# MSP432E401YTPDT_MCU.net
KiCad netlist of a schematic drawn in Altium Designer
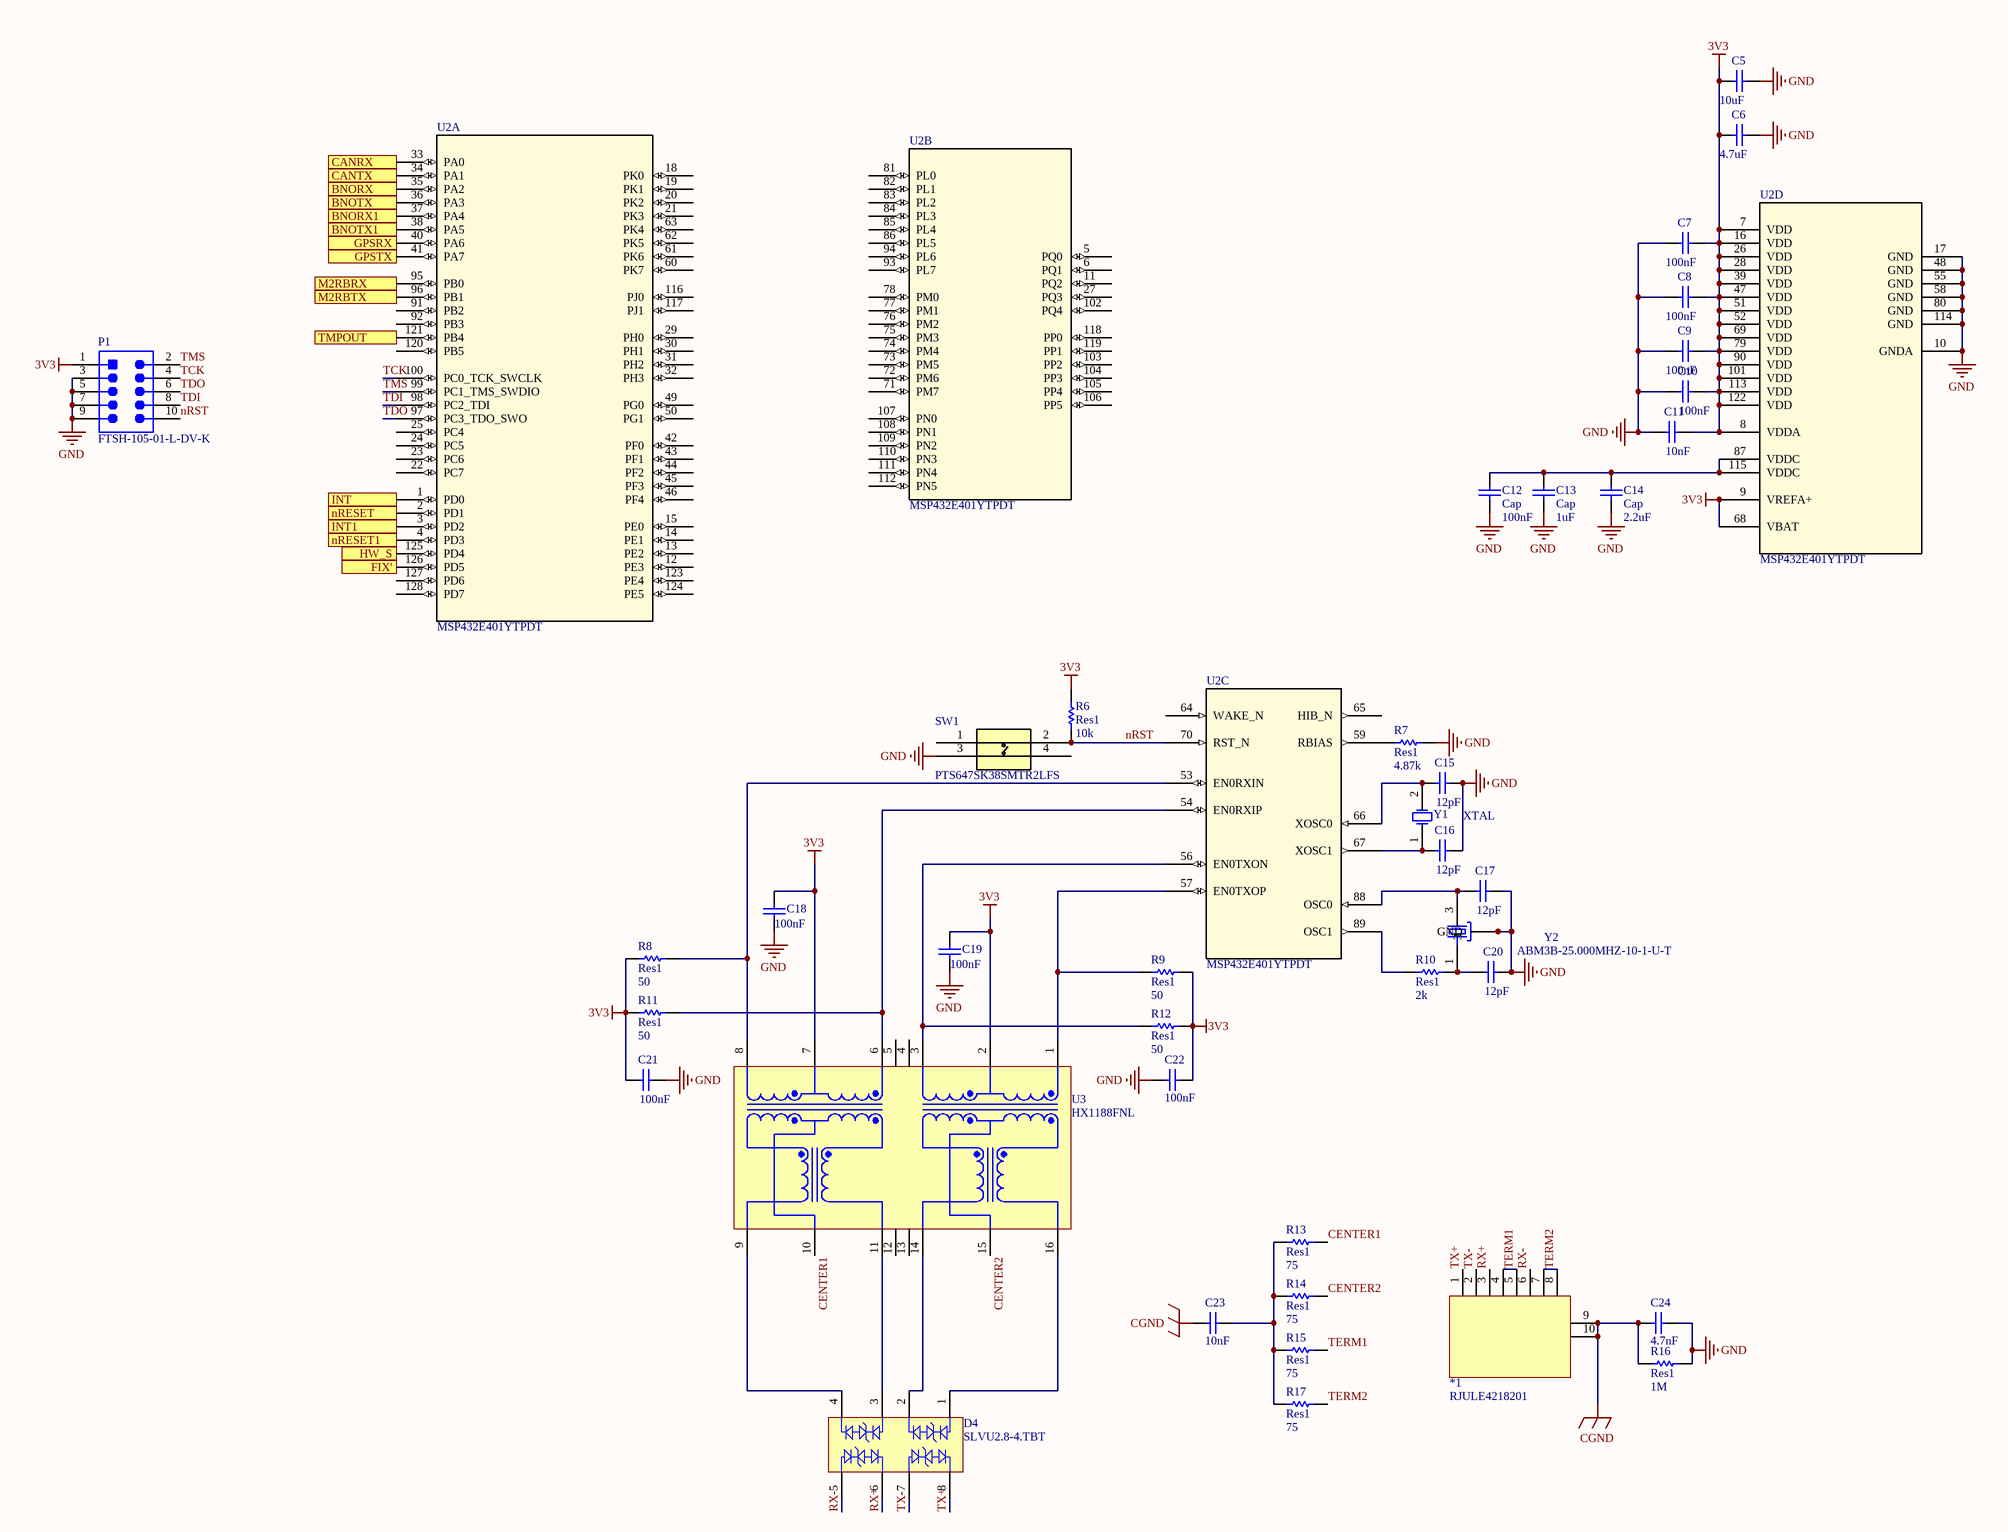
[diagram p0: MSP432E401YTPDT MCU.SchDoc]

(export (version "E")
  (design (tool "Eeschema 10.0.6"))
  (components
    (comp (ref "*1")
      (value "RJULE4218201")
      (footprint "RJULE4218201")
      (libsource (lib "RJULE4218201") (part "RJULE4218201"))
    )
    (comp (ref "C5")
      (value "10uF")
      (footprint "6-0805_M")
      (description "Capacitor")
      (fields (field (name "Comment") "Cap") (field (name "PUBLISHER") "Altium Limited"))
      (libsource (lib "Miscellaneous Devices") (part "Cap"))
    )
    (comp (ref "C6")
      (value "4.7uF")
      (footprint "6-0805_M")
      (description "Capacitor")
      (fields (field (name "Comment") "Cap") (field (name "PUBLISHER") "Altium Limited"))
      (libsource (lib "Miscellaneous Devices") (part "Cap"))
    )
    (comp (ref "C7")
      (value "100nF")
      (footprint "0402-A")
      (description "Capacitor")
      (fields (field (name "Comment") "Cap") (field (name "PUBLISHER") "Altium Limited"))
      (libsource (lib "Miscellaneous Devices") (part "Cap"))
    )
    (comp (ref "C8")
      (value "100nF")
      (footprint "0402-A")
      (description "Capacitor")
      (fields (field (name "Comment") "Cap") (field (name "PUBLISHER") "Altium Limited"))
      (libsource (lib "Miscellaneous Devices") (part "Cap"))
    )
    (comp (ref "C9")
      (value "100nF")
      (footprint "0402-A")
      (description "Capacitor")
      (fields (field (name "Comment") "Cap") (field (name "PUBLISHER") "Altium Limited"))
      (libsource (lib "Miscellaneous Devices") (part "Cap"))
    )
    (comp (ref "C10")
      (value "100nF")
      (footprint "0402-A")
      (description "Capacitor")
      (fields (field (name "Comment") "Cap") (field (name "PUBLISHER") "Altium Limited"))
      (libsource (lib "Miscellaneous Devices") (part "Cap"))
    )
    (comp (ref "C11")
      (value "10nF")
      (footprint "0402-A")
      (description "Capacitor")
      (fields (field (name "Comment") "Cap") (field (name "PUBLISHER") "Altium Limited"))
      (libsource (lib "Miscellaneous Devices") (part "Cap"))
    )
    (comp (ref "C12")
      (value "Cap")
      (footprint "0402-A")
      (description "Capacitor")
      (fields (field (name "ALTIUM_VALUE") "100nF") (field (name "PUBLISHER") "Altium Limited"))
      (libsource (lib "Miscellaneous Devices") (part "Cap"))
    )
    (comp (ref "C13")
      (value "Cap")
      (footprint "1608[0603]")
      (description "Capacitor")
      (fields (field (name "ALTIUM_VALUE") "1uF") (field (name "PUBLISHER") "Altium Limited"))
      (libsource (lib "Miscellaneous Devices") (part "Cap"))
    )
    (comp (ref "C14")
      (value "Cap")
      (footprint "1608[0603]")
      (description "Capacitor")
      (fields (field (name "ALTIUM_VALUE") "2.2uF") (field (name "PUBLISHER") "Altium Limited"))
      (libsource (lib "Miscellaneous Devices") (part "Cap"))
    )
    (comp (ref "C15")
      (value "12pF")
      (footprint "0402-A")
      (description "Capacitor")
      (fields (field (name "Comment") "Cap") (field (name "PUBLISHER") "Altium Limited"))
      (libsource (lib "Miscellaneous Devices") (part "Cap"))
    )
    (comp (ref "C16")
      (value "12pF")
      (footprint "0402-A")
      (description "Capacitor")
      (fields (field (name "Comment") "Cap") (field (name "PUBLISHER") "Altium Limited"))
      (libsource (lib "Miscellaneous Devices") (part "Cap"))
    )
    (comp (ref "C17")
      (value "12pF")
      (footprint "0402-A")
      (description "Capacitor")
      (fields (field (name "Comment") "Cap") (field (name "PUBLISHER") "Altium Limited"))
      (libsource (lib "Miscellaneous Devices") (part "Cap"))
    )
    (comp (ref "C18")
      (value "100nF")
      (footprint "0402-A")
      (description "Capacitor")
      (fields (field (name "Comment") "Cap") (field (name "PUBLISHER") "Altium Limited"))
      (libsource (lib "Miscellaneous Devices") (part "Cap"))
    )
    (comp (ref "C19")
      (value "100nF")
      (footprint "0402-A")
      (description "Capacitor")
      (fields (field (name "Comment") "Cap") (field (name "PUBLISHER") "Altium Limited"))
      (libsource (lib "Miscellaneous Devices") (part "Cap"))
    )
    (comp (ref "C20")
      (value "12pF")
      (footprint "0402-A")
      (description "Capacitor")
      (fields (field (name "Comment") "Cap") (field (name "PUBLISHER") "Altium Limited"))
      (libsource (lib "Miscellaneous Devices") (part "Cap"))
    )
    (comp (ref "C21")
      (value "100nF")
      (footprint "0402-A")
      (description "Capacitor")
      (fields (field (name "Comment") "Cap") (field (name "PUBLISHER") "Altium Limited"))
      (libsource (lib "Miscellaneous Devices") (part "Cap"))
    )
    (comp (ref "C22")
      (value "100nF")
      (footprint "0402-A")
      (description "Capacitor")
      (fields (field (name "Comment") "Cap") (field (name "PUBLISHER") "Altium Limited"))
      (libsource (lib "Miscellaneous Devices") (part "Cap"))
    )
    (comp (ref "C23")
      (value "10nF")
      (footprint "0402-A")
      (description "Capacitor")
      (fields (field (name "Comment") "Cap") (field (name "PUBLISHER") "Altium Limited"))
      (libsource (lib "Miscellaneous Devices") (part "Cap"))
    )
    (comp (ref "C24")
      (value "4.7nF")
      (footprint "C1206")
      (description "Capacitor")
      (fields (field (name "Comment") "Cap") (field (name "PUBLISHER") "Altium Limited"))
      (libsource (lib "Miscellaneous Devices") (part "Cap"))
    )
    (comp (ref "D4")
      (value "SLVU2.8-4.TBT")
      (footprint "SEMT-SO-8_V")
      (fields (field (name "MANUFACTURER") "Semtech"))
      (libsource (lib "Altium Content Vault") (part "SEMT-SLVU2.8-4-SO-8"))
    )
    (comp (ref "P1")
      (value "FTSH-105-01-L-DV-K")
      (footprint "SMTC-FTSH-105-01-L-DV-K_V")
      (description "Male Header, Pitch 1.27 mm, 2 x 5 Position, Height 6.25 mm")
      (fields (field (name "MANUFACTURER") "Samtec"))
      (libsource (lib "Altium Content Vault") (part "CN-2P-M-R10"))
    )
    (comp (ref "R6")
      (value "Res1")
      (footprint "0402-A")
      (description "Resistor")
      (fields (field (name "ALTIUM_VALUE") "10k") (field (name "PUBLISHER") "Altium Limited"))
      (libsource (lib "Miscellaneous Devices") (part "Res1"))
    )
    (comp (ref "R7")
      (value "Res1")
      (footprint "0402-A")
      (description "Resistor")
      (fields (field (name "ALTIUM_VALUE") "4.87k") (field (name "PUBLISHER") "Altium Limited"))
      (libsource (lib "Miscellaneous Devices") (part "Res1"))
    )
    (comp (ref "R8")
      (value "Res1")
      (footprint "0402-A")
      (description "Resistor")
      (fields (field (name "ALTIUM_VALUE") "50") (field (name "PUBLISHER") "Altium Limited"))
      (libsource (lib "Miscellaneous Devices") (part "Res1"))
    )
    (comp (ref "R9")
      (value "Res1")
      (footprint "0402-A")
      (description "Resistor")
      (fields (field (name "ALTIUM_VALUE") "50") (field (name "PUBLISHER") "Altium Limited"))
      (libsource (lib "Miscellaneous Devices") (part "Res1"))
    )
    (comp (ref "R10")
      (value "Res1")
      (footprint "0402-A")
      (description "Resistor")
      (fields (field (name "ALTIUM_VALUE") "2k") (field (name "PUBLISHER") "Altium Limited"))
      (libsource (lib "Miscellaneous Devices") (part "Res1"))
    )
    (comp (ref "R11")
      (value "Res1")
      (footprint "0402-A")
      (description "Resistor")
      (fields (field (name "ALTIUM_VALUE") "50") (field (name "PUBLISHER") "Altium Limited"))
      (libsource (lib "Miscellaneous Devices") (part "Res1"))
    )
    (comp (ref "R12")
      (value "Res1")
      (footprint "0402-A")
      (description "Resistor")
      (fields (field (name "ALTIUM_VALUE") "50") (field (name "PUBLISHER") "Altium Limited"))
      (libsource (lib "Miscellaneous Devices") (part "Res1"))
    )
    (comp (ref "R13")
      (value "Res1")
      (footprint "0402-A")
      (description "Resistor")
      (fields (field (name "ALTIUM_VALUE") "75") (field (name "PUBLISHER") "Altium Limited"))
      (libsource (lib "Miscellaneous Devices") (part "Res1"))
    )
    (comp (ref "R14")
      (value "Res1")
      (footprint "0402-A")
      (description "Resistor")
      (fields (field (name "ALTIUM_VALUE") "75") (field (name "PUBLISHER") "Altium Limited"))
      (libsource (lib "Miscellaneous Devices") (part "Res1"))
    )
    (comp (ref "R15")
      (value "Res1")
      (footprint "0402-A")
      (description "Resistor")
      (fields (field (name "ALTIUM_VALUE") "75") (field (name "PUBLISHER") "Altium Limited"))
      (libsource (lib "Miscellaneous Devices") (part "Res1"))
    )
    (comp (ref "R16")
      (value "Res1")
      (footprint "C1206")
      (description "Resistor")
      (fields (field (name "ALTIUM_VALUE") "1M") (field (name "PUBLISHER") "Altium Limited"))
      (libsource (lib "Miscellaneous Devices") (part "Res1"))
    )
    (comp (ref "R17")
      (value "Res1")
      (footprint "0402-A")
      (description "Resistor")
      (fields (field (name "ALTIUM_VALUE") "75") (field (name "PUBLISHER") "Altium Limited"))
      (libsource (lib "Miscellaneous Devices") (part "Res1"))
    )
    (comp (ref "SW1")
      (value "PTS647SK38SMTR2LFS")
      (footprint "PTS647SK38SMTR2LFS_CNK")
      (description "No Description Available")
      (fields (field (name "COPYRIGHT") "Copyright (C) 2018 Accelerated Designs. All rights reserved"))
      (libsource (lib "PTS 647 SK38 SMTR2 LFS") (part "PTS647SK38SMTR2LFS"))
    )
    (comp (ref "U2")
      (value "MSP432E401YTPDT")
      (footprint "PDT0128A")
      (description "No Description Available")
      (fields
        (field (name "MANUFACTURER") "Texas Instruments")
        (field (name "PARTNUMBER") "MSP432E401YTPDTR")
        (field (name "COPYRIGHT") "Copyright (C) 2018 Accelerated Designs. All rights reserved")
      )
      (libsource (lib "MSP432E401Y") (part "MSP432E401YTPDT"))
    )
    (comp (ref "U3")
      (value "HX1188FNL")
      (footprint "PULS-HX1188FNL-SMT-16_V")
      (description "Telecom Transformer 1:1/1:1, -40 to 85 degC, 16-Pin SMT, RoHS, Tube")
      (fields (field (name "MANUFACTURER") "Pulse Electronics"))
      (libsource (lib "Altium Content Vault") (part "PULS-HX1188FNL-16"))
    )
    (comp (ref "Y1")
      (value "XTAL")
      (footprint "FC-135 32.7680KA-AC0")
      (description "Crystal Oscillator")
      (fields (field (name "PUBLISHER") "Altium Limited"))
      (libsource (lib "Miscellaneous Devices") (part "XTAL"))
    )
    (comp (ref "Y2")
      (value "ABM3B-25.000MHZ-10-1-U-T")
      (footprint "OSCCC500X320X110-4N")
      (description "25MHz Â±10ppm Crystal 10pF 50 Ohms 4-SMD, No Lead")
      (fields (field (name "MF") "Abracon"))
      (libsource (lib "ABM3B-25.000MHZ-10-1-U-T") (part "ABM3B-25.000MHZ-10-1-U-T"))
    )
  )
  (nets
    (net (code "1") (name "/BNORX") (class "Default")
      (node (ref "U2") (pin "35") (pinfunction "PA2_35") (pintype "bidirectional"))
    )
    (net (code "2") (name "/BNORX1") (class "Default")
      (node (ref "U2") (pin "37") (pinfunction "PA4_37") (pintype "bidirectional"))
    )
    (net (code "3") (name "/BNOTX") (class "Default")
      (node (ref "U2") (pin "36") (pinfunction "PA3_36") (pintype "bidirectional"))
    )
    (net (code "4") (name "/BNOTX1") (class "Default")
      (node (ref "U2") (pin "38") (pinfunction "PA5_38") (pintype "bidirectional"))
    )
    (net (code "5") (name "/CANRX") (class "Default")
      (node (ref "U2") (pin "33") (pinfunction "PA0_33") (pintype "bidirectional"))
    )
    (net (code "6") (name "/CANTX") (class "Default")
      (node (ref "U2") (pin "34") (pinfunction "PA1_34") (pintype "bidirectional"))
    )
    (net (code "7") (name "/CENTER1") (class "Default")
      (node (ref "R13") (pin "2") (pinfunction "2_2") (pintype "passive"))
      (node (ref "U3") (pin "10") (pinfunction "CMT_10") (pintype "passive"))
    )
    (net (code "8") (name "/CENTER2") (class "Default")
      (node (ref "R14") (pin "2") (pinfunction "2_2") (pintype "passive"))
      (node (ref "U3") (pin "15") (pinfunction "CMT_15") (pintype "passive"))
    )
    (net (code "9") (name "/FIX'") (class "Default")
      (node (ref "U2") (pin "126") (pinfunction "PD5_126") (pintype "bidirectional"))
    )
    (net (code "10") (name "/GPSRX") (class "Default")
      (node (ref "U2") (pin "40") (pinfunction "PA6_40") (pintype "bidirectional"))
    )
    (net (code "11") (name "/GPSTX") (class "Default")
      (node (ref "U2") (pin "41") (pinfunction "PA7_41") (pintype "bidirectional"))
    )
    (net (code "12") (name "/HW_S") (class "Default")
      (node (ref "U2") (pin "125") (pinfunction "PD4_125") (pintype "bidirectional"))
    )
    (net (code "13") (name "/INT") (class "Default")
      (node (ref "U2") (pin "1") (pinfunction "PD0_1") (pintype "bidirectional"))
    )
    (net (code "14") (name "/INT1") (class "Default")
      (node (ref "U2") (pin "3") (pinfunction "PD2_3") (pintype "bidirectional"))
    )
    (net (code "15") (name "/M2RBRX") (class "Default")
      (node (ref "U2") (pin "95") (pinfunction "PB0_95") (pintype "bidirectional"))
    )
    (net (code "16") (name "/M2RBTX") (class "Default")
      (node (ref "U2") (pin "96") (pinfunction "PB1_96") (pintype "bidirectional"))
    )
    (net (code "17") (name "/RX+") (class "Default")
      (node (ref "*1") (pin "3") (pinfunction "13_3") (pintype "passive"))
      (node (ref "D4") (pin "6") (pinfunction "6_6") (pintype "passive"))
    )
    (net (code "18") (name "/RX-") (class "Default")
      (node (ref "*1") (pin "6") (pinfunction "16_6") (pintype "passive"))
      (node (ref "D4") (pin "5") (pinfunction "5_5") (pintype "passive"))
    )
    (net (code "19") (name "/TCK") (class "Default")
      (node (ref "P1") (pin "4") (pinfunction "4_4") (pintype "passive"))
      (node (ref "U2") (pin "100") (pinfunction "PC0_TCK_SWCLK_100") (pintype "bidirectional"))
    )
    (net (code "20") (name "/TDI") (class "Default")
      (node (ref "P1") (pin "8") (pinfunction "8_8") (pintype "passive"))
      (node (ref "U2") (pin "98") (pinfunction "PC2_TDI_98") (pintype "bidirectional"))
    )
    (net (code "21") (name "/TDO") (class "Default")
      (node (ref "P1") (pin "6") (pinfunction "6_6") (pintype "passive"))
      (node (ref "U2") (pin "97") (pinfunction "PC3_TDO_SWO_97") (pintype "bidirectional"))
    )
    (net (code "22") (name "/TERM1") (class "Default")
      (node (ref "*1") (pin "4") (pinfunction "14_4") (pintype "passive"))
      (node (ref "*1") (pin "5") (pinfunction "15_5") (pintype "passive"))
      (node (ref "R15") (pin "2") (pinfunction "2_2") (pintype "passive"))
    )
    (net (code "23") (name "/TERM2") (class "Default")
      (node (ref "*1") (pin "7") (pinfunction "17_7") (pintype "passive"))
      (node (ref "*1") (pin "8") (pinfunction "18_8") (pintype "passive"))
      (node (ref "R17") (pin "2") (pinfunction "2_2") (pintype "passive"))
    )
    (net (code "24") (name "/TMPOUT") (class "Default")
      (node (ref "U2") (pin "121") (pinfunction "PB4_121") (pintype "bidirectional"))
    )
    (net (code "25") (name "/TMS") (class "Default")
      (node (ref "P1") (pin "2") (pinfunction "2_2") (pintype "passive"))
      (node (ref "U2") (pin "99") (pinfunction "PC1_TMS_SWDIO_99") (pintype "bidirectional"))
    )
    (net (code "26") (name "/TX+") (class "Default")
      (node (ref "*1") (pin "1") (pinfunction "11_1") (pintype "passive"))
      (node (ref "D4") (pin "8") (pinfunction "8_8") (pintype "passive"))
    )
    (net (code "27") (name "/TX-") (class "Default")
      (node (ref "*1") (pin "2") (pinfunction "12_2") (pintype "passive"))
      (node (ref "D4") (pin "7") (pinfunction "7_7") (pintype "passive"))
    )
    (net (code "28") (name "/nRESET") (class "Default")
      (node (ref "U2") (pin "2") (pinfunction "PD1_2") (pintype "bidirectional"))
    )
    (net (code "29") (name "/nRESET1") (class "Default")
      (node (ref "U2") (pin "4") (pinfunction "PD3_4") (pintype "bidirectional"))
    )
    (net (code "30") (name "/nRST") (class "Default")
      (node (ref "P1") (pin "10") (pinfunction "10_10") (pintype "passive"))
      (node (ref "R6") (pin "2") (pinfunction "2_2") (pintype "passive"))
      (node (ref "SW1") (pin "2") (pinfunction "2_2") (pintype "passive"))
      (node (ref "U2") (pin "70") (pinfunction "RST_N_70") (pintype "input"))
    )
    (net (code "31") (name "3V3") (class "Default")
      (node (ref "C10") (pin "2") (pinfunction "2_2") (pintype "passive"))
      (node (ref "C11") (pin "2") (pinfunction "2_2") (pintype "passive"))
      (node (ref "C18") (pin "1") (pinfunction "1_1") (pintype "passive"))
      (node (ref "C19") (pin "1") (pinfunction "1_1") (pintype "passive"))
      (node (ref "C21") (pin "1") (pinfunction "1_1") (pintype "passive"))
      (node (ref "C22") (pin "1") (pinfunction "1_1") (pintype "passive"))
      (node (ref "C5") (pin "1") (pinfunction "1_1") (pintype "passive"))
      (node (ref "C6") (pin "1") (pinfunction "1_1") (pintype "passive"))
      (node (ref "C7") (pin "2") (pinfunction "2_2") (pintype "passive"))
      (node (ref "C8") (pin "2") (pinfunction "2_2") (pintype "passive"))
      (node (ref "C9") (pin "2") (pinfunction "2_2") (pintype "passive"))
      (node (ref "P1") (pin "1") (pinfunction "1_1") (pintype "passive"))
      (node (ref "R11") (pin "1") (pinfunction "1_1") (pintype "passive"))
      (node (ref "R12") (pin "1") (pinfunction "1_1") (pintype "passive"))
      (node (ref "R6") (pin "1") (pinfunction "1_1") (pintype "passive"))
      (node (ref "R8") (pin "1") (pinfunction "1_1") (pintype "passive"))
      (node (ref "R9") (pin "1") (pinfunction "1_1") (pintype "passive"))
      (node (ref "U2") (pin "101") (pinfunction "VDD_101") (pintype "power_in"))
      (node (ref "U2") (pin "113") (pinfunction "VDD_113") (pintype "power_in"))
      (node (ref "U2") (pin "122") (pinfunction "VDD_122") (pintype "power_in"))
      (node (ref "U2") (pin "16") (pinfunction "VDD_16") (pintype "power_in"))
      (node (ref "U2") (pin "26") (pinfunction "VDD_26") (pintype "power_in"))
      (node (ref "U2") (pin "28") (pinfunction "VDD_28") (pintype "power_in"))
      (node (ref "U2") (pin "39") (pinfunction "VDD_39") (pintype "power_in"))
      (node (ref "U2") (pin "47") (pinfunction "VDD_47") (pintype "power_in"))
      (node (ref "U2") (pin "51") (pinfunction "VDD_51") (pintype "power_in"))
      (node (ref "U2") (pin "52") (pinfunction "VDD_52") (pintype "power_in"))
      (node (ref "U2") (pin "68") (pinfunction "VBAT_68") (pintype "power_in"))
      (node (ref "U2") (pin "69") (pinfunction "VDD_69") (pintype "power_in"))
      (node (ref "U2") (pin "7") (pinfunction "VDD_7") (pintype "power_in"))
      (node (ref "U2") (pin "79") (pinfunction "VDD_79") (pintype "power_in"))
      (node (ref "U2") (pin "8") (pinfunction "VDDA_8") (pintype "power_in"))
      (node (ref "U2") (pin "9") (pinfunction "VREFA+_9") (pintype "power_in"))
      (node (ref "U2") (pin "90") (pinfunction "VDD_90") (pintype "power_in"))
      (node (ref "U3") (pin "2") (pinfunction "TCT_2") (pintype "passive"))
      (node (ref "U3") (pin "7") (pinfunction "RCT_7") (pintype "passive"))
    )
    (net (code "32") (name "CGND") (class "Default")
      (node (ref "*1") (pin "10") (pinfunction "10_10") (pintype "passive"))
      (node (ref "*1") (pin "9") (pinfunction "9_9") (pintype "passive"))
      (node (ref "C23") (pin "1") (pinfunction "1_1") (pintype "passive"))
      (node (ref "C24") (pin "1") (pinfunction "1_1") (pintype "passive"))
      (node (ref "R16") (pin "1") (pinfunction "1_1") (pintype "passive"))
    )
    (net (code "33") (name "GND") (class "Default")
      (node (ref "C10") (pin "1") (pinfunction "1_1") (pintype "passive"))
      (node (ref "C11") (pin "1") (pinfunction "1_1") (pintype "passive"))
      (node (ref "C12") (pin "1") (pinfunction "1_1") (pintype "passive"))
      (node (ref "C13") (pin "1") (pinfunction "1_1") (pintype "passive"))
      (node (ref "C14") (pin "1") (pinfunction "1_1") (pintype "passive"))
      (node (ref "C15") (pin "1") (pinfunction "1_1") (pintype "passive"))
      (node (ref "C16") (pin "1") (pinfunction "1_1") (pintype "passive"))
      (node (ref "C17") (pin "1") (pinfunction "1_1") (pintype "passive"))
      (node (ref "C18") (pin "2") (pinfunction "2_2") (pintype "passive"))
      (node (ref "C19") (pin "2") (pinfunction "2_2") (pintype "passive"))
      (node (ref "C20") (pin "1") (pinfunction "1_1") (pintype "passive"))
      (node (ref "C21") (pin "2") (pinfunction "2_2") (pintype "passive"))
      (node (ref "C22") (pin "2") (pinfunction "2_2") (pintype "passive"))
      (node (ref "C24") (pin "2") (pinfunction "2_2") (pintype "passive"))
      (node (ref "C5") (pin "2") (pinfunction "2_2") (pintype "passive"))
      (node (ref "C6") (pin "2") (pinfunction "2_2") (pintype "passive"))
      (node (ref "C7") (pin "1") (pinfunction "1_1") (pintype "passive"))
      (node (ref "C8") (pin "1") (pinfunction "1_1") (pintype "passive"))
      (node (ref "C9") (pin "1") (pinfunction "1_1") (pintype "passive"))
      (node (ref "P1") (pin "3") (pinfunction "3_3") (pintype "passive"))
      (node (ref "P1") (pin "5") (pinfunction "5_5") (pintype "passive"))
      (node (ref "P1") (pin "7") (pinfunction "7_7") (pintype "passive"))
      (node (ref "P1") (pin "9") (pinfunction "9_9") (pintype "passive"))
      (node (ref "R16") (pin "2") (pinfunction "2_2") (pintype "passive"))
      (node (ref "R7") (pin "1") (pinfunction "1_1") (pintype "passive"))
      (node (ref "SW1") (pin "3") (pinfunction "3_3") (pintype "passive"))
      (node (ref "U2") (pin "10") (pinfunction "GNDA_10") (pintype "power_in"))
      (node (ref "U2") (pin "114") (pinfunction "GND_114") (pintype "power_in"))
      (node (ref "U2") (pin "17") (pinfunction "GND_17") (pintype "power_in"))
      (node (ref "U2") (pin "48") (pinfunction "GND_48") (pintype "power_in"))
      (node (ref "U2") (pin "55") (pinfunction "GND_55") (pintype "power_in"))
      (node (ref "U2") (pin "58") (pinfunction "GND_58") (pintype "power_in"))
      (node (ref "U2") (pin "80") (pinfunction "GND_80") (pintype "power_in"))
      (node (ref "Y2") (pin "2") (pinfunction "GND_2") (pintype "passive"))
      (node (ref "Y2") (pin "4") (pinfunction "GND_4") (pintype "passive"))
    )
    (net (code "34") (name "Net-(C12-Pad2)") (class "Default")
      (node (ref "C12") (pin "2") (pinfunction "2_2") (pintype "passive"))
      (node (ref "C13") (pin "2") (pinfunction "2_2") (pintype "passive"))
      (node (ref "C14") (pin "2") (pinfunction "2_2") (pintype "passive"))
      (node (ref "U2") (pin "115") (pinfunction "VDDC_115") (pintype "power_in"))
      (node (ref "U2") (pin "87") (pinfunction "VDDC_87") (pintype "power_in"))
    )
    (net (code "35") (name "Net-(C20-Pad2)") (class "Default")
      (node (ref "C20") (pin "2") (pinfunction "2_2") (pintype "passive"))
      (node (ref "R10") (pin "2") (pinfunction "2_2") (pintype "passive"))
      (node (ref "Y2") (pin "1") (pinfunction "1_1") (pintype "passive"))
    )
    (net (code "36") (name "Net-(C23-Pad2)") (class "Default")
      (node (ref "C23") (pin "2") (pinfunction "2_2") (pintype "passive"))
      (node (ref "R13") (pin "1") (pinfunction "1_1") (pintype "passive"))
      (node (ref "R14") (pin "1") (pinfunction "1_1") (pintype "passive"))
      (node (ref "R15") (pin "1") (pinfunction "1_1") (pintype "passive"))
      (node (ref "R17") (pin "1") (pinfunction "1_1") (pintype "passive"))
    )
    (net (code "37") (name "Net-(U2C-EN0RXIN)") (class "Default")
      (node (ref "R8") (pin "2") (pinfunction "2_2") (pintype "passive"))
      (node (ref "U2") (pin "53") (pinfunction "EN0RXIN_53") (pintype "bidirectional"))
      (node (ref "U3") (pin "8") (pinfunction "RD-_8") (pintype "passive"))
    )
    (net (code "38") (name "Net-(U2C-EN0RXIP)") (class "Default")
      (node (ref "R11") (pin "2") (pinfunction "2_2") (pintype "passive"))
      (node (ref "U2") (pin "54") (pinfunction "EN0RXIP_54") (pintype "bidirectional"))
      (node (ref "U3") (pin "6") (pinfunction "RD+_6") (pintype "passive"))
    )
    (net (code "39") (name "Net-(U2C-EN0TXON)") (class "Default")
      (node (ref "R12") (pin "2") (pinfunction "2_2") (pintype "passive"))
      (node (ref "U2") (pin "56") (pinfunction "EN0TXON_56") (pintype "bidirectional"))
      (node (ref "U3") (pin "3") (pinfunction "TD-_3") (pintype "passive"))
    )
    (net (code "40") (name "Net-(U2C-EN0TXOP)") (class "Default")
      (node (ref "R9") (pin "2") (pinfunction "2_2") (pintype "passive"))
      (node (ref "U2") (pin "57") (pinfunction "EN0TXOP_57") (pintype "bidirectional"))
      (node (ref "U3") (pin "1") (pinfunction "TD+_1") (pintype "passive"))
    )
    (net (code "41") (name "Net-(U2C-OSC0)") (class "Default")
      (node (ref "C17") (pin "2") (pinfunction "2_2") (pintype "passive"))
      (node (ref "U2") (pin "88") (pinfunction "OSC0_88") (pintype "input"))
      (node (ref "Y2") (pin "3") (pinfunction "3_3") (pintype "passive"))
    )
    (net (code "42") (name "Net-(U2C-OSC1)") (class "Default")
      (node (ref "R10") (pin "1") (pinfunction "1_1") (pintype "passive"))
      (node (ref "U2") (pin "89") (pinfunction "OSC1_89") (pintype "output"))
    )
    (net (code "43") (name "Net-(U2C-RBIAS)") (class "Default")
      (node (ref "R7") (pin "2") (pinfunction "2_2") (pintype "passive"))
      (node (ref "U2") (pin "59") (pinfunction "RBIAS_59") (pintype "output"))
    )
    (net (code "44") (name "Net-(U2C-XOSC0)") (class "Default")
      (node (ref "C15") (pin "2") (pinfunction "2_2") (pintype "passive"))
      (node (ref "U2") (pin "66") (pinfunction "XOSC0_66") (pintype "input"))
      (node (ref "Y1") (pin "2") (pinfunction "OSC2_2") (pintype "passive"))
    )
    (net (code "45") (name "Net-(U2C-XOSC1)") (class "Default")
      (node (ref "C16") (pin "2") (pinfunction "2_2") (pintype "passive"))
      (node (ref "U2") (pin "67") (pinfunction "XOSC1_67") (pintype "output"))
      (node (ref "Y1") (pin "1") (pinfunction "OSC1_1") (pintype "passive"))
    )
    (net (code "46") (name "Net-(U3-RX+)") (class "Default")
      (node (ref "D4") (pin "3") (pinfunction "3_3") (pintype "passive"))
      (node (ref "U3") (pin "11") (pinfunction "RX+_11") (pintype "passive"))
    )
    (net (code "47") (name "Net-(U3-RX-)") (class "Default")
      (node (ref "D4") (pin "4") (pinfunction "4_4") (pintype "passive"))
      (node (ref "U3") (pin "9") (pinfunction "RX-_9") (pintype "passive"))
    )
    (net (code "48") (name "Net-(U3-TX+)") (class "Default")
      (node (ref "D4") (pin "1") (pinfunction "1_1") (pintype "passive"))
      (node (ref "U3") (pin "16") (pinfunction "TX+_16") (pintype "passive"))
    )
    (net (code "49") (name "Net-(U3-TX-)") (class "Default")
      (node (ref "D4") (pin "2") (pinfunction "2_2") (pintype "passive"))
      (node (ref "U3") (pin "14") (pinfunction "TX-_14") (pintype "passive"))
    )
    (net (code "50") (name "unconnected-(SW1-Pad1)") (class "Default")
      (node (ref "SW1") (pin "1") (pinfunction "1_1") (pintype "passive"))
    )
    (net (code "51") (name "unconnected-(SW1-Pad4)") (class "Default")
      (node (ref "SW1") (pin "4") (pinfunction "4_4") (pintype "passive"))
    )
    (net (code "52") (name "unconnected-(U2A-PB2-Pad91)") (class "Default")
      (node (ref "U2") (pin "91") (pinfunction "PB2_91") (pintype "bidirectional"))
    )
    (net (code "53") (name "unconnected-(U2A-PB3-Pad92)") (class "Default")
      (node (ref "U2") (pin "92") (pinfunction "PB3_92") (pintype "bidirectional"))
    )
    (net (code "54") (name "unconnected-(U2A-PB5-Pad120)") (class "Default")
      (node (ref "U2") (pin "120") (pinfunction "PB5_120") (pintype "bidirectional"))
    )
    (net (code "55") (name "unconnected-(U2A-PC4-Pad25)") (class "Default")
      (node (ref "U2") (pin "25") (pinfunction "PC4_25") (pintype "bidirectional"))
    )
    (net (code "56") (name "unconnected-(U2A-PC5-Pad24)") (class "Default")
      (node (ref "U2") (pin "24") (pinfunction "PC5_24") (pintype "bidirectional"))
    )
    (net (code "57") (name "unconnected-(U2A-PC6-Pad23)") (class "Default")
      (node (ref "U2") (pin "23") (pinfunction "PC6_23") (pintype "bidirectional"))
    )
    (net (code "58") (name "unconnected-(U2A-PC7-Pad22)") (class "Default")
      (node (ref "U2") (pin "22") (pinfunction "PC7_22") (pintype "bidirectional"))
    )
    (net (code "59") (name "unconnected-(U2A-PD6-Pad127)") (class "Default")
      (node (ref "U2") (pin "127") (pinfunction "PD6_127") (pintype "bidirectional"))
    )
    (net (code "60") (name "unconnected-(U2A-PD7-Pad128)") (class "Default")
      (node (ref "U2") (pin "128") (pinfunction "PD7_128") (pintype "bidirectional"))
    )
    (net (code "61") (name "unconnected-(U2A-PE0-Pad15)") (class "Default")
      (node (ref "U2") (pin "15") (pinfunction "PE0_15") (pintype "bidirectional"))
    )
    (net (code "62") (name "unconnected-(U2A-PE1-Pad14)") (class "Default")
      (node (ref "U2") (pin "14") (pinfunction "PE1_14") (pintype "bidirectional"))
    )
    (net (code "63") (name "unconnected-(U2A-PE2-Pad13)") (class "Default")
      (node (ref "U2") (pin "13") (pinfunction "PE2_13") (pintype "bidirectional"))
    )
    (net (code "64") (name "unconnected-(U2A-PE3-Pad12)") (class "Default")
      (node (ref "U2") (pin "12") (pinfunction "PE3_12") (pintype "bidirectional"))
    )
    (net (code "65") (name "unconnected-(U2A-PE4-Pad123)") (class "Default")
      (node (ref "U2") (pin "123") (pinfunction "PE4_123") (pintype "bidirectional"))
    )
    (net (code "66") (name "unconnected-(U2A-PE5-Pad124)") (class "Default")
      (node (ref "U2") (pin "124") (pinfunction "PE5_124") (pintype "bidirectional"))
    )
    (net (code "67") (name "unconnected-(U2A-PF0-Pad42)") (class "Default")
      (node (ref "U2") (pin "42") (pinfunction "PF0_42") (pintype "bidirectional"))
    )
    (net (code "68") (name "unconnected-(U2A-PF1-Pad43)") (class "Default")
      (node (ref "U2") (pin "43") (pinfunction "PF1_43") (pintype "bidirectional"))
    )
    (net (code "69") (name "unconnected-(U2A-PF2-Pad44)") (class "Default")
      (node (ref "U2") (pin "44") (pinfunction "PF2_44") (pintype "bidirectional"))
    )
    (net (code "70") (name "unconnected-(U2A-PF3-Pad45)") (class "Default")
      (node (ref "U2") (pin "45") (pinfunction "PF3_45") (pintype "bidirectional"))
    )
    (net (code "71") (name "unconnected-(U2A-PF4-Pad46)") (class "Default")
      (node (ref "U2") (pin "46") (pinfunction "PF4_46") (pintype "bidirectional"))
    )
    (net (code "72") (name "unconnected-(U2A-PG0-Pad49)") (class "Default")
      (node (ref "U2") (pin "49") (pinfunction "PG0_49") (pintype "bidirectional"))
    )
    (net (code "73") (name "unconnected-(U2A-PG1-Pad50)") (class "Default")
      (node (ref "U2") (pin "50") (pinfunction "PG1_50") (pintype "bidirectional"))
    )
    (net (code "74") (name "unconnected-(U2A-PH0-Pad29)") (class "Default")
      (node (ref "U2") (pin "29") (pinfunction "PH0_29") (pintype "bidirectional"))
    )
    (net (code "75") (name "unconnected-(U2A-PH1-Pad30)") (class "Default")
      (node (ref "U2") (pin "30") (pinfunction "PH1_30") (pintype "bidirectional"))
    )
    (net (code "76") (name "unconnected-(U2A-PH2-Pad31)") (class "Default")
      (node (ref "U2") (pin "31") (pinfunction "PH2_31") (pintype "bidirectional"))
    )
    (net (code "77") (name "unconnected-(U2A-PH3-Pad32)") (class "Default")
      (node (ref "U2") (pin "32") (pinfunction "PH3_32") (pintype "bidirectional"))
    )
    (net (code "78") (name "unconnected-(U2A-PJ0-Pad116)") (class "Default")
      (node (ref "U2") (pin "116") (pinfunction "PJ0_116") (pintype "bidirectional"))
    )
    (net (code "79") (name "unconnected-(U2A-PJ1-Pad117)") (class "Default")
      (node (ref "U2") (pin "117") (pinfunction "PJ1_117") (pintype "bidirectional"))
    )
    (net (code "80") (name "unconnected-(U2A-PK0-Pad18)") (class "Default")
      (node (ref "U2") (pin "18") (pinfunction "PK0_18") (pintype "bidirectional"))
    )
    (net (code "81") (name "unconnected-(U2A-PK1-Pad19)") (class "Default")
      (node (ref "U2") (pin "19") (pinfunction "PK1_19") (pintype "bidirectional"))
    )
    (net (code "82") (name "unconnected-(U2A-PK2-Pad20)") (class "Default")
      (node (ref "U2") (pin "20") (pinfunction "PK2_20") (pintype "bidirectional"))
    )
    (net (code "83") (name "unconnected-(U2A-PK3-Pad21)") (class "Default")
      (node (ref "U2") (pin "21") (pinfunction "PK3_21") (pintype "bidirectional"))
    )
    (net (code "84") (name "unconnected-(U2A-PK4-Pad63)") (class "Default")
      (node (ref "U2") (pin "63") (pinfunction "PK4_63") (pintype "bidirectional"))
    )
    (net (code "85") (name "unconnected-(U2A-PK5-Pad62)") (class "Default")
      (node (ref "U2") (pin "62") (pinfunction "PK5_62") (pintype "bidirectional"))
    )
    (net (code "86") (name "unconnected-(U2A-PK6-Pad61)") (class "Default")
      (node (ref "U2") (pin "61") (pinfunction "PK6_61") (pintype "bidirectional"))
    )
    (net (code "87") (name "unconnected-(U2A-PK7-Pad60)") (class "Default")
      (node (ref "U2") (pin "60") (pinfunction "PK7_60") (pintype "bidirectional"))
    )
    (net (code "88") (name "unconnected-(U2B-PL0-Pad81)") (class "Default")
      (node (ref "U2") (pin "81") (pinfunction "PL0_81") (pintype "bidirectional"))
    )
    (net (code "89") (name "unconnected-(U2B-PL1-Pad82)") (class "Default")
      (node (ref "U2") (pin "82") (pinfunction "PL1_82") (pintype "bidirectional"))
    )
    (net (code "90") (name "unconnected-(U2B-PL2-Pad83)") (class "Default")
      (node (ref "U2") (pin "83") (pinfunction "PL2_83") (pintype "bidirectional"))
    )
    (net (code "91") (name "unconnected-(U2B-PL3-Pad84)") (class "Default")
      (node (ref "U2") (pin "84") (pinfunction "PL3_84") (pintype "bidirectional"))
    )
    (net (code "92") (name "unconnected-(U2B-PL4-Pad85)") (class "Default")
      (node (ref "U2") (pin "85") (pinfunction "PL4_85") (pintype "bidirectional"))
    )
    (net (code "93") (name "unconnected-(U2B-PL5-Pad86)") (class "Default")
      (node (ref "U2") (pin "86") (pinfunction "PL5_86") (pintype "bidirectional"))
    )
    (net (code "94") (name "unconnected-(U2B-PL6-Pad94)") (class "Default")
      (node (ref "U2") (pin "94") (pinfunction "PL6_94") (pintype "bidirectional"))
    )
    (net (code "95") (name "unconnected-(U2B-PL7-Pad93)") (class "Default")
      (node (ref "U2") (pin "93") (pinfunction "PL7_93") (pintype "bidirectional"))
    )
    (net (code "96") (name "unconnected-(U2B-PM0-Pad78)") (class "Default")
      (node (ref "U2") (pin "78") (pinfunction "PM0_78") (pintype "bidirectional"))
    )
    (net (code "97") (name "unconnected-(U2B-PM1-Pad77)") (class "Default")
      (node (ref "U2") (pin "77") (pinfunction "PM1_77") (pintype "bidirectional"))
    )
    (net (code "98") (name "unconnected-(U2B-PM2-Pad76)") (class "Default")
      (node (ref "U2") (pin "76") (pinfunction "PM2_76") (pintype "bidirectional"))
    )
    (net (code "99") (name "unconnected-(U2B-PM3-Pad75)") (class "Default")
      (node (ref "U2") (pin "75") (pinfunction "PM3_75") (pintype "bidirectional"))
    )
    (net (code "100") (name "unconnected-(U2B-PM4-Pad74)") (class "Default")
      (node (ref "U2") (pin "74") (pinfunction "PM4_74") (pintype "bidirectional"))
    )
    (net (code "101") (name "unconnected-(U2B-PM5-Pad73)") (class "Default")
      (node (ref "U2") (pin "73") (pinfunction "PM5_73") (pintype "bidirectional"))
    )
    (net (code "102") (name "unconnected-(U2B-PM6-Pad72)") (class "Default")
      (node (ref "U2") (pin "72") (pinfunction "PM6_72") (pintype "bidirectional"))
    )
    (net (code "103") (name "unconnected-(U2B-PM7-Pad71)") (class "Default")
      (node (ref "U2") (pin "71") (pinfunction "PM7_71") (pintype "bidirectional"))
    )
    (net (code "104") (name "unconnected-(U2B-PN0-Pad107)") (class "Default")
      (node (ref "U2") (pin "107") (pinfunction "PN0_107") (pintype "bidirectional"))
    )
    (net (code "105") (name "unconnected-(U2B-PN1-Pad108)") (class "Default")
      (node (ref "U2") (pin "108") (pinfunction "PN1_108") (pintype "bidirectional"))
    )
    (net (code "106") (name "unconnected-(U2B-PN2-Pad109)") (class "Default")
      (node (ref "U2") (pin "109") (pinfunction "PN2_109") (pintype "bidirectional"))
    )
    (net (code "107") (name "unconnected-(U2B-PN3-Pad110)") (class "Default")
      (node (ref "U2") (pin "110") (pinfunction "PN3_110") (pintype "bidirectional"))
    )
    (net (code "108") (name "unconnected-(U2B-PN4-Pad111)") (class "Default")
      (node (ref "U2") (pin "111") (pinfunction "PN4_111") (pintype "bidirectional"))
    )
    (net (code "109") (name "unconnected-(U2B-PN5-Pad112)") (class "Default")
      (node (ref "U2") (pin "112") (pinfunction "PN5_112") (pintype "bidirectional"))
    )
    (net (code "110") (name "unconnected-(U2B-PP0-Pad118)") (class "Default")
      (node (ref "U2") (pin "118") (pinfunction "PP0_118") (pintype "bidirectional"))
    )
    (net (code "111") (name "unconnected-(U2B-PP1-Pad119)") (class "Default")
      (node (ref "U2") (pin "119") (pinfunction "PP1_119") (pintype "bidirectional"))
    )
    (net (code "112") (name "unconnected-(U2B-PP2-Pad103)") (class "Default")
      (node (ref "U2") (pin "103") (pinfunction "PP2_103") (pintype "bidirectional"))
    )
    (net (code "113") (name "unconnected-(U2B-PP3-Pad104)") (class "Default")
      (node (ref "U2") (pin "104") (pinfunction "PP3_104") (pintype "bidirectional"))
    )
    (net (code "114") (name "unconnected-(U2B-PP4-Pad105)") (class "Default")
      (node (ref "U2") (pin "105") (pinfunction "PP4_105") (pintype "bidirectional"))
    )
    (net (code "115") (name "unconnected-(U2B-PP5-Pad106)") (class "Default")
      (node (ref "U2") (pin "106") (pinfunction "PP5_106") (pintype "bidirectional"))
    )
    (net (code "116") (name "unconnected-(U2B-PQ0-Pad5)") (class "Default")
      (node (ref "U2") (pin "5") (pinfunction "PQ0_5") (pintype "bidirectional"))
    )
    (net (code "117") (name "unconnected-(U2B-PQ1-Pad6)") (class "Default")
      (node (ref "U2") (pin "6") (pinfunction "PQ1_6") (pintype "bidirectional"))
    )
    (net (code "118") (name "unconnected-(U2B-PQ2-Pad11)") (class "Default")
      (node (ref "U2") (pin "11") (pinfunction "PQ2_11") (pintype "bidirectional"))
    )
    (net (code "119") (name "unconnected-(U2B-PQ3-Pad27)") (class "Default")
      (node (ref "U2") (pin "27") (pinfunction "PQ3_27") (pintype "bidirectional"))
    )
    (net (code "120") (name "unconnected-(U2B-PQ4-Pad102)") (class "Default")
      (node (ref "U2") (pin "102") (pinfunction "PQ4_102") (pintype "bidirectional"))
    )
    (net (code "121") (name "unconnected-(U2C-HIB_N-Pad65)") (class "Default")
      (node (ref "U2") (pin "65") (pinfunction "HIB_N_65") (pintype "output"))
    )
    (net (code "122") (name "unconnected-(U2C-WAKE_N-Pad64)") (class "Default")
      (node (ref "U2") (pin "64") (pinfunction "WAKE_N_64") (pintype "input"))
    )
    (net (code "123") (name "unconnected-(U3-NC-Pad4)") (class "Default")
      (node (ref "U3") (pin "4") (pinfunction "NC_4") (pintype "passive"))
    )
    (net (code "124") (name "unconnected-(U3-NC-Pad5)") (class "Default")
      (node (ref "U3") (pin "5") (pinfunction "NC_5") (pintype "passive"))
    )
    (net (code "125") (name "unconnected-(U3-NC-Pad12)") (class "Default")
      (node (ref "U3") (pin "12") (pinfunction "NC_12") (pintype "passive"))
    )
    (net (code "126") (name "unconnected-(U3-NC-Pad13)") (class "Default")
      (node (ref "U3") (pin "13") (pinfunction "NC_13") (pintype "passive"))
    )
  )
)
